# nano_motor.net
KiCad netlist of a schematic drawn in EAGLE
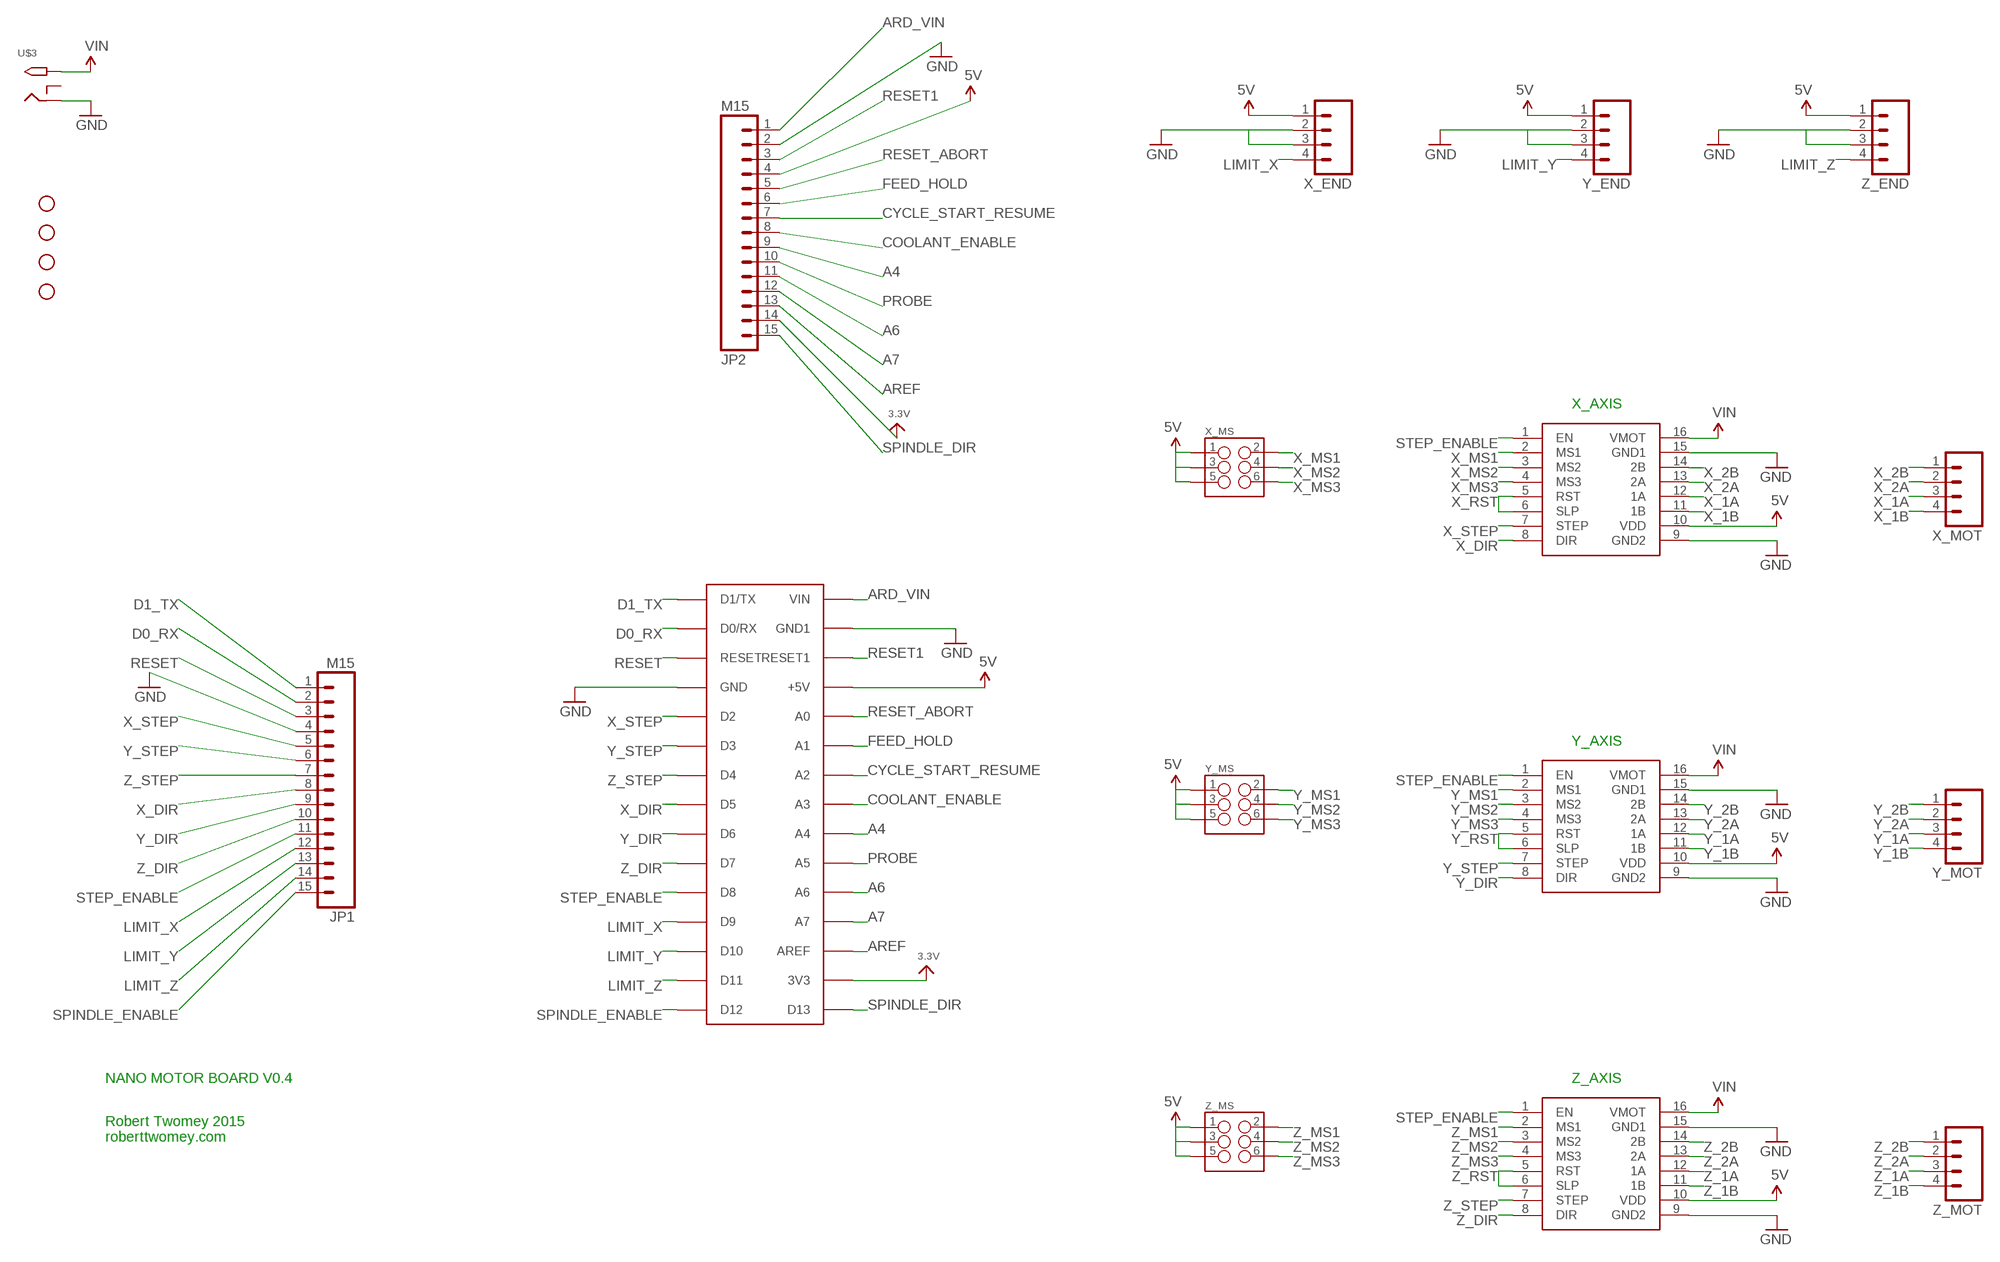
[diagram p0: schematic, sheet 1]

(export (version "E")
  (design (tool "Eeschema 10.0.6"))
  (components
    (comp (ref "JP1")
      (value "M15")
      (footprint "eagle-import:1X15")
      (libsource (lib "eagle-import") (part "M15"))
    )
    (comp (ref "JP2")
      (value "M15")
      (footprint "eagle-import:1X15")
      (libsource (lib "eagle-import") (part "M15"))
    )
    (comp (ref "NANO")
      (value "ARDUINONANO")
      (footprint "eagle-import:PDIP-32")
      (libsource (lib "eagle-import") (part "ARDUINONANO"))
    )
    (comp (ref "STANDOFF1")
      (value "STAND-OFF")
      (footprint "eagle-import:STAND-OFF")
      (libsource (lib "eagle-import") (part "STAND-OFF"))
    )
    (comp (ref "STANDOFF2")
      (value "STAND-OFF")
      (footprint "eagle-import:STAND-OFF")
      (libsource (lib "eagle-import") (part "STAND-OFF"))
    )
    (comp (ref "STANDOFF3")
      (value "STAND-OFF")
      (footprint "eagle-import:STAND-OFF")
      (libsource (lib "eagle-import") (part "STAND-OFF"))
    )
    (comp (ref "STANDOFF4")
      (value "STAND-OFF")
      (footprint "eagle-import:STAND-OFF")
      (libsource (lib "eagle-import") (part "STAND-OFF"))
    )
    (comp (ref "U$3")
      (value "2.1MMJACKTHM")
      (footprint "eagle-import:PJ-102A")
      (libsource (lib "eagle-import") (part "2.1MMJACKTHM"))
    )
    (comp (ref "X_AXIS")
      (value "POLOLUESTEPPERDRIVER")
      (footprint "eagle-import:DIL16")
      (libsource (lib "eagle-import") (part "POLOLUESTEPPERDRIVER"))
    )
    (comp (ref "X_END")
      (value "M04PTH")
      (footprint "eagle-import:1X04")
      (libsource (lib "eagle-import") (part "M04PTH"))
    )
    (comp (ref "X_MOT")
      (value "M04PTH")
      (footprint "eagle-import:1X04")
      (libsource (lib "eagle-import") (part "M04PTH"))
    )
    (comp (ref "X_MS")
      (value "M03X22X3_SILK_SM")
      (footprint "eagle-import:2X3")
      (libsource (lib "eagle-import") (part "M03X22X3_SILK_SM"))
    )
    (comp (ref "Y_AXIS")
      (value "POLOLUESTEPPERDRIVER")
      (footprint "eagle-import:DIL16")
      (libsource (lib "eagle-import") (part "POLOLUESTEPPERDRIVER"))
    )
    (comp (ref "Y_END")
      (value "M04PTH")
      (footprint "eagle-import:1X04")
      (libsource (lib "eagle-import") (part "M04PTH"))
    )
    (comp (ref "Y_MOT")
      (value "M04PTH")
      (footprint "eagle-import:1X04")
      (libsource (lib "eagle-import") (part "M04PTH"))
    )
    (comp (ref "Y_MS")
      (value "M03X22X3_SILK_SM")
      (footprint "eagle-import:2X3")
      (libsource (lib "eagle-import") (part "M03X22X3_SILK_SM"))
    )
    (comp (ref "Z_AXIS")
      (value "POLOLUESTEPPERDRIVER")
      (footprint "eagle-import:DIL16")
      (libsource (lib "eagle-import") (part "POLOLUESTEPPERDRIVER"))
    )
    (comp (ref "Z_END")
      (value "M04PTH")
      (footprint "eagle-import:1X04")
      (libsource (lib "eagle-import") (part "M04PTH"))
    )
    (comp (ref "Z_MOT")
      (value "M04PTH")
      (footprint "eagle-import:1X04")
      (libsource (lib "eagle-import") (part "M04PTH"))
    )
    (comp (ref "Z_MS")
      (value "M03X22X3_SILK_SM")
      (footprint "eagle-import:2X3")
      (libsource (lib "eagle-import") (part "M03X22X3_SILK_SM"))
    )
  )
  (nets
    (net (code "1") (name "/A4") (class "Default")
      (node (ref "JP2") (pin "9") (pinfunction "9_9") (pintype "passive"))
      (node (ref "NANO") (pin "A4") (pinfunction "A4_A4") (pintype "bidirectional"))
    )
    (net (code "2") (name "/A6") (class "Default")
      (node (ref "JP2") (pin "11") (pinfunction "11_11") (pintype "passive"))
      (node (ref "NANO") (pin "A6") (pinfunction "A6_A6") (pintype "bidirectional"))
    )
    (net (code "3") (name "/A7") (class "Default")
      (node (ref "JP2") (pin "12") (pinfunction "12_12") (pintype "passive"))
      (node (ref "NANO") (pin "A7") (pinfunction "A7_A7") (pintype "bidirectional"))
    )
    (net (code "4") (name "/ARD_VIN") (class "Default")
      (node (ref "JP2") (pin "1") (pinfunction "1_1") (pintype "passive"))
      (node (ref "NANO") (pin "VIN") (pinfunction "VIN_VIN") (pintype "bidirectional"))
    )
    (net (code "5") (name "/AREF") (class "Default")
      (node (ref "JP2") (pin "13") (pinfunction "13_13") (pintype "passive"))
      (node (ref "NANO") (pin "AREF") (pinfunction "AREF_AREF") (pintype "bidirectional"))
    )
    (net (code "6") (name "/COOLANT_ENABLE") (class "Default")
      (node (ref "JP2") (pin "8") (pinfunction "8_8") (pintype "passive"))
      (node (ref "NANO") (pin "A3") (pinfunction "A3_A3") (pintype "bidirectional"))
    )
    (net (code "7") (name "/CYCLE_START_RESUME") (class "Default")
      (node (ref "JP2") (pin "7") (pinfunction "7_7") (pintype "passive"))
      (node (ref "NANO") (pin "A2") (pinfunction "A2_A2") (pintype "bidirectional"))
    )
    (net (code "8") (name "/D0_RX") (class "Default")
      (node (ref "JP1") (pin "2") (pinfunction "2_2") (pintype "passive"))
      (node (ref "NANO") (pin "D0/RX") (pinfunction "D0/RX_D0/RX") (pintype "bidirectional"))
    )
    (net (code "9") (name "/D1_TX") (class "Default")
      (node (ref "JP1") (pin "1") (pinfunction "1_1") (pintype "passive"))
      (node (ref "NANO") (pin "D1/TX") (pinfunction "D1/TX_D1/TX") (pintype "bidirectional"))
    )
    (net (code "10") (name "/FEED_HOLD") (class "Default")
      (node (ref "JP2") (pin "6") (pinfunction "6_6") (pintype "passive"))
      (node (ref "NANO") (pin "A1") (pinfunction "A1_A1") (pintype "bidirectional"))
    )
    (net (code "11") (name "/LIMIT_X") (class "Default")
      (node (ref "JP1") (pin "12") (pinfunction "12_12") (pintype "passive"))
      (node (ref "NANO") (pin "D9") (pinfunction "D9_D9") (pintype "bidirectional"))
      (node (ref "X_END") (pin "4") (pinfunction "4_4") (pintype "passive"))
    )
    (net (code "12") (name "/LIMIT_Y") (class "Default")
      (node (ref "JP1") (pin "13") (pinfunction "13_13") (pintype "passive"))
      (node (ref "NANO") (pin "D10") (pinfunction "D10_D10") (pintype "bidirectional"))
      (node (ref "Y_END") (pin "4") (pinfunction "4_4") (pintype "passive"))
    )
    (net (code "13") (name "/LIMIT_Z") (class "Default")
      (node (ref "JP1") (pin "14") (pinfunction "14_14") (pintype "passive"))
      (node (ref "NANO") (pin "D11") (pinfunction "D11_D11") (pintype "bidirectional"))
      (node (ref "Z_END") (pin "4") (pinfunction "4_4") (pintype "passive"))
    )
    (net (code "14") (name "/PROBE") (class "Default")
      (node (ref "JP2") (pin "10") (pinfunction "10_10") (pintype "passive"))
      (node (ref "NANO") (pin "A5") (pinfunction "A5_A5") (pintype "bidirectional"))
    )
    (net (code "15") (name "/RESET") (class "Default")
      (node (ref "JP1") (pin "3") (pinfunction "3_3") (pintype "passive"))
      (node (ref "NANO") (pin "RESET") (pinfunction "RESET_RESET") (pintype "bidirectional"))
    )
    (net (code "16") (name "/RESET1") (class "Default")
      (node (ref "JP2") (pin "3") (pinfunction "3_3") (pintype "passive"))
      (node (ref "NANO") (pin "RESET1") (pinfunction "RESET1_RESET1") (pintype "bidirectional"))
    )
    (net (code "17") (name "/RESET_ABORT") (class "Default")
      (node (ref "JP2") (pin "5") (pinfunction "5_5") (pintype "passive"))
      (node (ref "NANO") (pin "A0") (pinfunction "A0_A0") (pintype "bidirectional"))
    )
    (net (code "18") (name "/SPINDLE_DIR") (class "Default")
      (node (ref "JP2") (pin "15") (pinfunction "15_15") (pintype "passive"))
      (node (ref "NANO") (pin "D13") (pinfunction "D13_D13") (pintype "bidirectional"))
    )
    (net (code "19") (name "/SPINDLE_ENABLE") (class "Default")
      (node (ref "JP1") (pin "15") (pinfunction "15_15") (pintype "passive"))
      (node (ref "NANO") (pin "D12") (pinfunction "D12_D12") (pintype "bidirectional"))
    )
    (net (code "20") (name "/STEP_ENABLE") (class "Default")
      (node (ref "JP1") (pin "11") (pinfunction "11_11") (pintype "passive"))
      (node (ref "NANO") (pin "D8") (pinfunction "D8_D8") (pintype "bidirectional"))
      (node (ref "X_AXIS") (pin "1") (pinfunction "EN_1") (pintype "input"))
      (node (ref "Y_AXIS") (pin "1") (pinfunction "EN_1") (pintype "input"))
      (node (ref "Z_AXIS") (pin "1") (pinfunction "EN_1") (pintype "input"))
    )
    (net (code "21") (name "/X_1A") (class "Default")
      (node (ref "X_AXIS") (pin "12") (pinfunction "1A_12") (pintype "output"))
      (node (ref "X_MOT") (pin "3") (pinfunction "3_3") (pintype "passive"))
    )
    (net (code "22") (name "/X_1B") (class "Default")
      (node (ref "X_AXIS") (pin "11") (pinfunction "1B_11") (pintype "output"))
      (node (ref "X_MOT") (pin "4") (pinfunction "4_4") (pintype "passive"))
    )
    (net (code "23") (name "/X_2A") (class "Default")
      (node (ref "X_AXIS") (pin "13") (pinfunction "2A_13") (pintype "output"))
      (node (ref "X_MOT") (pin "2") (pinfunction "2_2") (pintype "passive"))
    )
    (net (code "24") (name "/X_2B") (class "Default")
      (node (ref "X_AXIS") (pin "14") (pinfunction "2B_14") (pintype "output"))
      (node (ref "X_MOT") (pin "1") (pinfunction "1_1") (pintype "passive"))
    )
    (net (code "25") (name "/X_DIR") (class "Default")
      (node (ref "JP1") (pin "8") (pinfunction "8_8") (pintype "passive"))
      (node (ref "NANO") (pin "D5") (pinfunction "D5_D5") (pintype "bidirectional"))
      (node (ref "X_AXIS") (pin "8") (pinfunction "DIR_8") (pintype "input"))
    )
    (net (code "26") (name "/X_MS1") (class "Default")
      (node (ref "X_AXIS") (pin "2") (pinfunction "MS1_2") (pintype "input"))
      (node (ref "X_MS") (pin "2") (pinfunction "2_2") (pintype "bidirectional"))
    )
    (net (code "27") (name "/X_MS2") (class "Default")
      (node (ref "X_AXIS") (pin "3") (pinfunction "MS2_3") (pintype "input"))
      (node (ref "X_MS") (pin "4") (pinfunction "4_4") (pintype "bidirectional"))
    )
    (net (code "28") (name "/X_MS3") (class "Default")
      (node (ref "X_AXIS") (pin "4") (pinfunction "MS3_4") (pintype "input"))
      (node (ref "X_MS") (pin "6") (pinfunction "6_6") (pintype "bidirectional"))
    )
    (net (code "29") (name "/X_RST") (class "Default")
      (node (ref "X_AXIS") (pin "5") (pinfunction "RST_5") (pintype "input"))
      (node (ref "X_AXIS") (pin "6") (pinfunction "SLP_6") (pintype "input"))
    )
    (net (code "30") (name "/X_STEP") (class "Default")
      (node (ref "JP1") (pin "5") (pinfunction "5_5") (pintype "passive"))
      (node (ref "NANO") (pin "D2") (pinfunction "D2_D2") (pintype "bidirectional"))
      (node (ref "X_AXIS") (pin "7") (pinfunction "STEP_7") (pintype "input"))
    )
    (net (code "31") (name "/Y_1A") (class "Default")
      (node (ref "Y_AXIS") (pin "12") (pinfunction "1A_12") (pintype "output"))
      (node (ref "Y_MOT") (pin "3") (pinfunction "3_3") (pintype "passive"))
    )
    (net (code "32") (name "/Y_1B") (class "Default")
      (node (ref "Y_AXIS") (pin "11") (pinfunction "1B_11") (pintype "output"))
      (node (ref "Y_MOT") (pin "4") (pinfunction "4_4") (pintype "passive"))
    )
    (net (code "33") (name "/Y_2A") (class "Default")
      (node (ref "Y_AXIS") (pin "13") (pinfunction "2A_13") (pintype "output"))
      (node (ref "Y_MOT") (pin "2") (pinfunction "2_2") (pintype "passive"))
    )
    (net (code "34") (name "/Y_2B") (class "Default")
      (node (ref "Y_AXIS") (pin "14") (pinfunction "2B_14") (pintype "output"))
      (node (ref "Y_MOT") (pin "1") (pinfunction "1_1") (pintype "passive"))
    )
    (net (code "35") (name "/Y_DIR") (class "Default")
      (node (ref "JP1") (pin "9") (pinfunction "9_9") (pintype "passive"))
      (node (ref "NANO") (pin "D6") (pinfunction "D6_D6") (pintype "bidirectional"))
      (node (ref "Y_AXIS") (pin "8") (pinfunction "DIR_8") (pintype "input"))
    )
    (net (code "36") (name "/Y_MS1") (class "Default")
      (node (ref "Y_AXIS") (pin "2") (pinfunction "MS1_2") (pintype "input"))
      (node (ref "Y_MS") (pin "2") (pinfunction "2_2") (pintype "bidirectional"))
    )
    (net (code "37") (name "/Y_MS2") (class "Default")
      (node (ref "Y_AXIS") (pin "3") (pinfunction "MS2_3") (pintype "input"))
      (node (ref "Y_MS") (pin "4") (pinfunction "4_4") (pintype "bidirectional"))
    )
    (net (code "38") (name "/Y_MS3") (class "Default")
      (node (ref "Y_AXIS") (pin "4") (pinfunction "MS3_4") (pintype "input"))
      (node (ref "Y_MS") (pin "6") (pinfunction "6_6") (pintype "bidirectional"))
    )
    (net (code "39") (name "/Y_RST") (class "Default")
      (node (ref "Y_AXIS") (pin "5") (pinfunction "RST_5") (pintype "input"))
      (node (ref "Y_AXIS") (pin "6") (pinfunction "SLP_6") (pintype "input"))
    )
    (net (code "40") (name "/Y_STEP") (class "Default")
      (node (ref "JP1") (pin "6") (pinfunction "6_6") (pintype "passive"))
      (node (ref "NANO") (pin "D3") (pinfunction "D3_D3") (pintype "bidirectional"))
      (node (ref "Y_AXIS") (pin "7") (pinfunction "STEP_7") (pintype "input"))
    )
    (net (code "41") (name "/Z_1A") (class "Default")
      (node (ref "Z_AXIS") (pin "12") (pinfunction "1A_12") (pintype "output"))
      (node (ref "Z_MOT") (pin "3") (pinfunction "3_3") (pintype "passive"))
    )
    (net (code "42") (name "/Z_1B") (class "Default")
      (node (ref "Z_AXIS") (pin "11") (pinfunction "1B_11") (pintype "output"))
      (node (ref "Z_MOT") (pin "4") (pinfunction "4_4") (pintype "passive"))
    )
    (net (code "43") (name "/Z_2A") (class "Default")
      (node (ref "Z_AXIS") (pin "13") (pinfunction "2A_13") (pintype "output"))
      (node (ref "Z_MOT") (pin "2") (pinfunction "2_2") (pintype "passive"))
    )
    (net (code "44") (name "/Z_2B") (class "Default")
      (node (ref "Z_AXIS") (pin "14") (pinfunction "2B_14") (pintype "output"))
      (node (ref "Z_MOT") (pin "1") (pinfunction "1_1") (pintype "passive"))
    )
    (net (code "45") (name "/Z_DIR") (class "Default")
      (node (ref "JP1") (pin "10") (pinfunction "10_10") (pintype "passive"))
      (node (ref "NANO") (pin "D7") (pinfunction "D7_D7") (pintype "bidirectional"))
      (node (ref "Z_AXIS") (pin "8") (pinfunction "DIR_8") (pintype "input"))
    )
    (net (code "46") (name "/Z_MS1") (class "Default")
      (node (ref "Z_AXIS") (pin "2") (pinfunction "MS1_2") (pintype "input"))
      (node (ref "Z_MS") (pin "2") (pinfunction "2_2") (pintype "bidirectional"))
    )
    (net (code "47") (name "/Z_MS2") (class "Default")
      (node (ref "Z_AXIS") (pin "3") (pinfunction "MS2_3") (pintype "input"))
      (node (ref "Z_MS") (pin "4") (pinfunction "4_4") (pintype "bidirectional"))
    )
    (net (code "48") (name "/Z_MS3") (class "Default")
      (node (ref "Z_AXIS") (pin "4") (pinfunction "MS3_4") (pintype "input"))
      (node (ref "Z_MS") (pin "6") (pinfunction "6_6") (pintype "bidirectional"))
    )
    (net (code "49") (name "/Z_RST") (class "Default")
      (node (ref "Z_AXIS") (pin "5") (pinfunction "RST_5") (pintype "input"))
      (node (ref "Z_AXIS") (pin "6") (pinfunction "SLP_6") (pintype "input"))
    )
    (net (code "50") (name "/Z_STEP") (class "Default")
      (node (ref "JP1") (pin "7") (pinfunction "7_7") (pintype "passive"))
      (node (ref "NANO") (pin "D4") (pinfunction "D4_D4") (pintype "bidirectional"))
      (node (ref "Z_AXIS") (pin "7") (pinfunction "STEP_7") (pintype "input"))
    )
    (net (code "51") (name "3.3V") (class "Default")
      (node (ref "JP2") (pin "14") (pinfunction "14_14") (pintype "passive"))
      (node (ref "NANO") (pin "3V3") (pinfunction "3V3_3V3") (pintype "bidirectional"))
    )
    (net (code "52") (name "5V") (class "Default")
      (node (ref "JP2") (pin "4") (pinfunction "4_4") (pintype "passive"))
      (node (ref "NANO") (pin "+5V") (pinfunction "+5V_+5V") (pintype "bidirectional"))
      (node (ref "X_AXIS") (pin "10") (pinfunction "VDD_10") (pintype "power_in"))
      (node (ref "X_END") (pin "1") (pinfunction "1_1") (pintype "passive"))
      (node (ref "X_MS") (pin "1") (pinfunction "1_1") (pintype "bidirectional"))
      (node (ref "X_MS") (pin "3") (pinfunction "3_3") (pintype "bidirectional"))
      (node (ref "X_MS") (pin "5") (pinfunction "5_5") (pintype "bidirectional"))
      (node (ref "Y_AXIS") (pin "10") (pinfunction "VDD_10") (pintype "power_in"))
      (node (ref "Y_END") (pin "1") (pinfunction "1_1") (pintype "passive"))
      (node (ref "Y_MS") (pin "1") (pinfunction "1_1") (pintype "bidirectional"))
      (node (ref "Y_MS") (pin "3") (pinfunction "3_3") (pintype "bidirectional"))
      (node (ref "Y_MS") (pin "5") (pinfunction "5_5") (pintype "bidirectional"))
      (node (ref "Z_AXIS") (pin "10") (pinfunction "VDD_10") (pintype "power_in"))
      (node (ref "Z_END") (pin "1") (pinfunction "1_1") (pintype "passive"))
      (node (ref "Z_MS") (pin "1") (pinfunction "1_1") (pintype "bidirectional"))
      (node (ref "Z_MS") (pin "3") (pinfunction "3_3") (pintype "bidirectional"))
      (node (ref "Z_MS") (pin "5") (pinfunction "5_5") (pintype "bidirectional"))
    )
    (net (code "53") (name "GND") (class "Default")
      (node (ref "JP1") (pin "4") (pinfunction "4_4") (pintype "passive"))
      (node (ref "JP2") (pin "2") (pinfunction "2_2") (pintype "passive"))
      (node (ref "NANO") (pin "GND") (pinfunction "GND_GND") (pintype "bidirectional"))
      (node (ref "NANO") (pin "GND1") (pinfunction "GND1_GND1") (pintype "bidirectional"))
      (node (ref "U$3") (pin "RING") (pinfunction "RING_RING") (pintype "bidirectional"))
      (node (ref "X_AXIS") (pin "15") (pinfunction "GND1_15") (pintype "power_in"))
      (node (ref "X_AXIS") (pin "9") (pinfunction "GND2_9") (pintype "power_in"))
      (node (ref "X_END") (pin "2") (pinfunction "2_2") (pintype "passive"))
      (node (ref "X_END") (pin "3") (pinfunction "3_3") (pintype "passive"))
      (node (ref "Y_AXIS") (pin "15") (pinfunction "GND1_15") (pintype "power_in"))
      (node (ref "Y_AXIS") (pin "9") (pinfunction "GND2_9") (pintype "power_in"))
      (node (ref "Y_END") (pin "2") (pinfunction "2_2") (pintype "passive"))
      (node (ref "Y_END") (pin "3") (pinfunction "3_3") (pintype "passive"))
      (node (ref "Z_AXIS") (pin "15") (pinfunction "GND1_15") (pintype "power_in"))
      (node (ref "Z_AXIS") (pin "9") (pinfunction "GND2_9") (pintype "power_in"))
      (node (ref "Z_END") (pin "2") (pinfunction "2_2") (pintype "passive"))
      (node (ref "Z_END") (pin "3") (pinfunction "3_3") (pintype "passive"))
    )
    (net (code "54") (name "VIN") (class "Default")
      (node (ref "U$3") (pin "TIP") (pinfunction "TIP_TIP") (pintype "bidirectional"))
      (node (ref "X_AXIS") (pin "16") (pinfunction "VMOT_16") (pintype "power_in"))
      (node (ref "Y_AXIS") (pin "16") (pinfunction "VMOT_16") (pintype "power_in"))
      (node (ref "Z_AXIS") (pin "16") (pinfunction "VMOT_16") (pintype "power_in"))
    )
    (net (code "55") (name "unconnected-(U$3-PadRING_SW)") (class "Default")
      (node (ref "U$3") (pin "RING_SW") (pinfunction "RING_SW_RING_SW") (pintype "bidirectional"))
    )
  )
)
